# flame_sensor_final.net
KiCad netlist of a schematic drawn in EAGLE
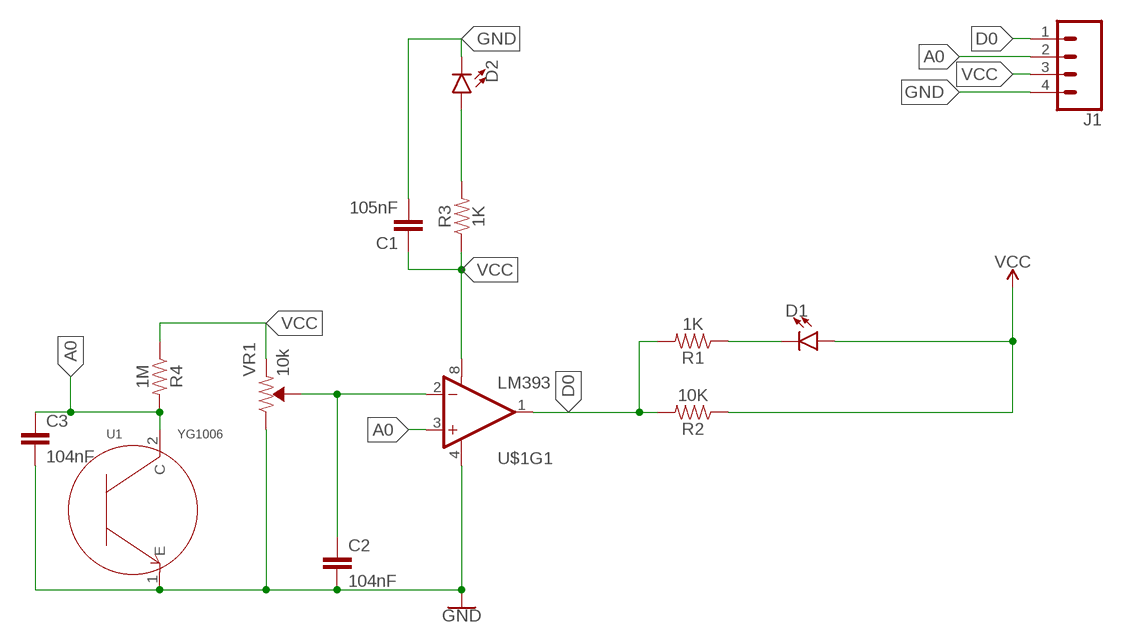
[diagram p0: schematic, sheet 1]

(export (version "E")
  (design (tool "Eeschema 10.0.6"))
  (components
    (comp (ref "C1")
      (value "105nF")
      (footprint "eagle-import:1206")
      (libsource (lib "eagle-import") (part "2.2UF-1206-50V-10%"))
    )
    (comp (ref "C2")
      (value "104nF")
      (footprint "eagle-import:1206")
      (libsource (lib "eagle-import") (part "2.2UF-1206-50V-10%"))
    )
    (comp (ref "C3")
      (value "104nF")
      (footprint "eagle-import:1206")
      (libsource (lib "eagle-import") (part "2.2UF-1206-50V-10%"))
    )
    (comp (ref "D1")
      (value "LED1206")
      (footprint "eagle-import:LED-1206")
      (libsource (lib "eagle-import") (part "LED1206"))
    )
    (comp (ref "D2")
      (value "LED1206")
      (footprint "eagle-import:LED-1206")
      (libsource (lib "eagle-import") (part "LED1206"))
    )
    (comp (ref "J1")
      (value "CONN_04")
      (footprint "eagle-import:1X04")
      (libsource (lib "eagle-import") (part "CONN_04"))
    )
    (comp (ref "R1")
      (value "1K")
      (footprint "eagle-import:0603")
      (libsource (lib "eagle-import") (part "0.05OHM-0603-1/5W-1%"))
    )
    (comp (ref "R2")
      (value "10K")
      (footprint "eagle-import:0603")
      (libsource (lib "eagle-import") (part "0.05OHM-0603-1/5W-1%"))
    )
    (comp (ref "R3")
      (value "1K")
      (footprint "eagle-import:0603")
      (libsource (lib "eagle-import") (part "0.05OHM-0603-1/5W-1%"))
    )
    (comp (ref "R4")
      (value "1M")
      (footprint "eagle-import:0603")
      (libsource (lib "eagle-import") (part "0.05OHM-0603-1/5W-1%"))
    )
    (comp (ref "U$1")
      (value "LM393")
      (footprint "eagle-import:SO08")
      (libsource (lib "eagle-import") (part "LM393"))
    )
    (comp (ref "U1")
      (value "YG1006")
      (footprint "eagle-import:2P-2.54-5MM")
      (libsource (lib "eagle-import") (part "YG1006'YG1006'"))
    )
    (comp (ref "VR1")
      (value "10k")
      (footprint "eagle-import:TRIMPOT-SMD-5MM")
      (libsource (lib "eagle-import") (part "TRIMPOT-SMD-5MM-CLOSED-1/4W-20%"))
    )
  )
  (nets
    (net (code "1") (name "A0") (class "Default")
      (node (ref "C3") (pin "1") (pinfunction "1_1") (pintype "passive"))
      (node (ref "J1") (pin "2") (pinfunction "2_2") (pintype "passive"))
      (node (ref "R4") (pin "2") (pinfunction "2_2") (pintype "passive"))
      (node (ref "U$1") (pin "3") (pinfunction "+IN_3") (pintype "input"))
      (node (ref "U1") (pin "2") (pinfunction "C_2") (pintype "bidirectional"))
    )
    (net (code "2") (name "D0") (class "Default")
      (node (ref "J1") (pin "1") (pinfunction "1_1") (pintype "passive"))
      (node (ref "R1") (pin "2") (pinfunction "2_2") (pintype "passive"))
      (node (ref "R2") (pin "2") (pinfunction "2_2") (pintype "passive"))
      (node (ref "U$1") (pin "1") (pinfunction "OUT_1") (pintype "output"))
    )
    (net (code "3") (name "GND") (class "Default")
      (node (ref "C1") (pin "2") (pinfunction "2_2") (pintype "passive"))
      (node (ref "C2") (pin "2") (pinfunction "2_2") (pintype "passive"))
      (node (ref "C3") (pin "2") (pinfunction "2_2") (pintype "passive"))
      (node (ref "D2") (pin "C") (pinfunction "C_C") (pintype "passive"))
      (node (ref "J1") (pin "4") (pinfunction "4_4") (pintype "passive"))
      (node (ref "U$1") (pin "4") (pinfunction "V-_4") (pintype "power_in"))
      (node (ref "U1") (pin "1") (pinfunction "E_1") (pintype "bidirectional"))
      (node (ref "VR1") (pin "C") (pinfunction "CW_C") (pintype "passive"))
    )
    (net (code "4") (name "Net-(D1-PadC)") (class "Default")
      (node (ref "D1") (pin "C") (pinfunction "C_C") (pintype "passive"))
      (node (ref "R1") (pin "1") (pinfunction "1_1") (pintype "passive"))
    )
    (net (code "5") (name "Net-(D2-PadA)") (class "Default")
      (node (ref "D2") (pin "A") (pinfunction "A_A") (pintype "passive"))
      (node (ref "R3") (pin "2") (pinfunction "2_2") (pintype "passive"))
    )
    (net (code "6") (name "Net-(U$1A--IN)") (class "Default")
      (node (ref "C2") (pin "1") (pinfunction "1_1") (pintype "passive"))
      (node (ref "U$1") (pin "2") (pinfunction "-IN_2") (pintype "input"))
      (node (ref "VR1") (pin "B") (pinfunction "WIPER_B") (pintype "passive"))
    )
    (net (code "7") (name "VCC") (class "Default")
      (node (ref "C1") (pin "1") (pinfunction "1_1") (pintype "passive"))
      (node (ref "D1") (pin "A") (pinfunction "A_A") (pintype "passive"))
      (node (ref "J1") (pin "3") (pinfunction "3_3") (pintype "passive"))
      (node (ref "R2") (pin "1") (pinfunction "1_1") (pintype "passive"))
      (node (ref "R3") (pin "1") (pinfunction "1_1") (pintype "passive"))
      (node (ref "R4") (pin "1") (pinfunction "1_1") (pintype "passive"))
      (node (ref "U$1") (pin "8") (pinfunction "V+_8") (pintype "power_in"))
      (node (ref "VR1") (pin "A") (pinfunction "CCW_A") (pintype "passive"))
    )
  )
)
